# 6-Sensors.net
KiCad netlist of a schematic drawn in Altium Designer
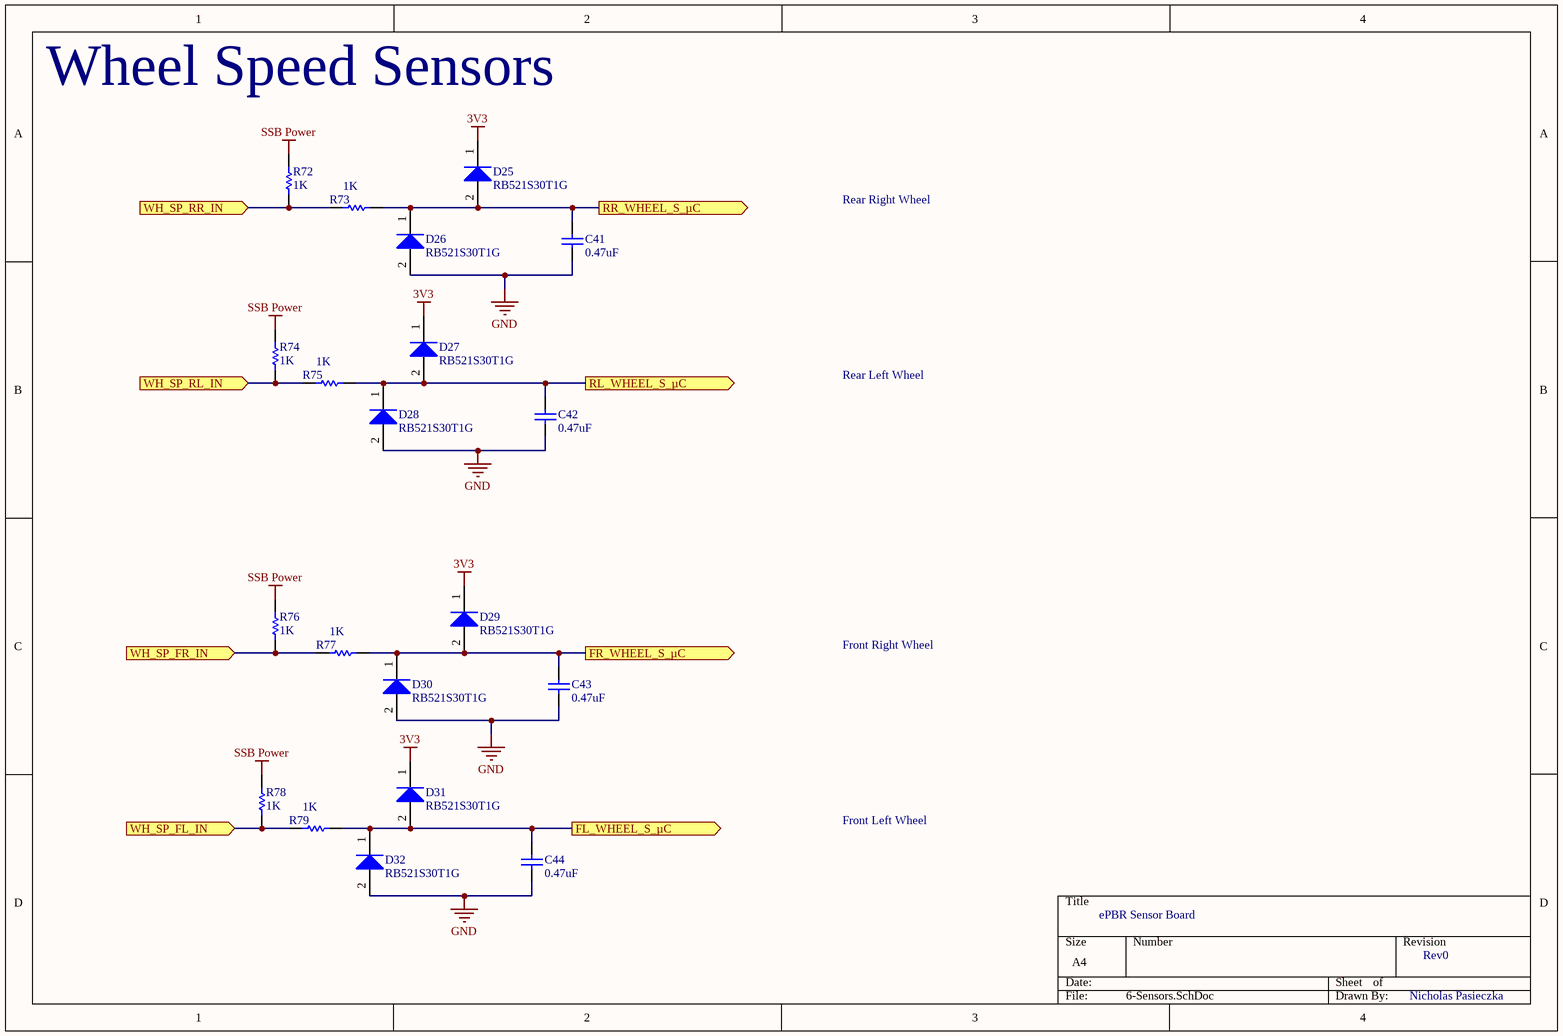
[diagram p0: 6-Sensors.SchDoc]

(export (version "E")
  (design (tool "Eeschema 10.0.6"))
  (components
    (comp (ref "C41")
      (value "0.47uF")
      (footprint "1608[0603]")
      (description "Capacitor")
      (fields (field (name "Comment") "Cap") (field (name "PUBLISHER") "Altium Limited"))
      (libsource (lib "Miscellaneous Devices") (part "Cap"))
    )
    (comp (ref "C42")
      (value "0.47uF")
      (footprint "1608[0603]")
      (description "Capacitor")
      (fields (field (name "Comment") "Cap") (field (name "PUBLISHER") "Altium Limited"))
      (libsource (lib "Miscellaneous Devices") (part "Cap"))
    )
    (comp (ref "C43")
      (value "0.47uF")
      (footprint "1608[0603]")
      (description "Capacitor")
      (fields (field (name "Comment") "Cap") (field (name "PUBLISHER") "Altium Limited"))
      (libsource (lib "Miscellaneous Devices") (part "Cap"))
    )
    (comp (ref "C44")
      (value "0.47uF")
      (footprint "1608[0603]")
      (description "Capacitor")
      (fields (field (name "Comment") "Cap") (field (name "PUBLISHER") "Altium Limited"))
      (libsource (lib "Miscellaneous Devices") (part "Cap"))
    )
    (comp (ref "D25")
      (value "RB521S30T1G")
      (footprint "ONSC-SOD-523-2-502-01_V")
      (description "Schottky Barrier Diode, 2-Pin SOD-523, Pb-Free, Tape and Reel")
      (fields (field (name "MANUFACTURER") "On Semiconductor"))
      (libsource (lib "Altium Content Vault") (part "ONSC-D-K1A2-2"))
    )
    (comp (ref "D26")
      (value "RB521S30T1G")
      (footprint "ONSC-SOD-523-2-502-01_V")
      (description "Schottky Barrier Diode, 2-Pin SOD-523, Pb-Free, Tape and Reel")
      (fields (field (name "MANUFACTURER") "On Semiconductor"))
      (libsource (lib "Altium Content Vault") (part "ONSC-D-K1A2-2"))
    )
    (comp (ref "D27")
      (value "RB521S30T1G")
      (footprint "ONSC-SOD-523-2-502-01_V")
      (description "Schottky Barrier Diode, 2-Pin SOD-523, Pb-Free, Tape and Reel")
      (fields (field (name "MANUFACTURER") "On Semiconductor"))
      (libsource (lib "Altium Content Vault") (part "ONSC-D-K1A2-2"))
    )
    (comp (ref "D28")
      (value "RB521S30T1G")
      (footprint "ONSC-SOD-523-2-502-01_V")
      (description "Schottky Barrier Diode, 2-Pin SOD-523, Pb-Free, Tape and Reel")
      (fields (field (name "MANUFACTURER") "On Semiconductor"))
      (libsource (lib "Altium Content Vault") (part "ONSC-D-K1A2-2"))
    )
    (comp (ref "D29")
      (value "RB521S30T1G")
      (footprint "ONSC-SOD-523-2-502-01_V")
      (description "Schottky Barrier Diode, 2-Pin SOD-523, Pb-Free, Tape and Reel")
      (fields (field (name "MANUFACTURER") "On Semiconductor"))
      (libsource (lib "Altium Content Vault") (part "ONSC-D-K1A2-2"))
    )
    (comp (ref "D30")
      (value "RB521S30T1G")
      (footprint "ONSC-SOD-523-2-502-01_V")
      (description "Schottky Barrier Diode, 2-Pin SOD-523, Pb-Free, Tape and Reel")
      (fields (field (name "MANUFACTURER") "On Semiconductor"))
      (libsource (lib "Altium Content Vault") (part "ONSC-D-K1A2-2"))
    )
    (comp (ref "D31")
      (value "RB521S30T1G")
      (footprint "ONSC-SOD-523-2-502-01_V")
      (description "Schottky Barrier Diode, 2-Pin SOD-523, Pb-Free, Tape and Reel")
      (fields (field (name "MANUFACTURER") "On Semiconductor"))
      (libsource (lib "Altium Content Vault") (part "ONSC-D-K1A2-2"))
    )
    (comp (ref "D32")
      (value "RB521S30T1G")
      (footprint "ONSC-SOD-523-2-502-01_V")
      (description "Schottky Barrier Diode, 2-Pin SOD-523, Pb-Free, Tape and Reel")
      (fields (field (name "MANUFACTURER") "On Semiconductor"))
      (libsource (lib "Altium Content Vault") (part "ONSC-D-K1A2-2"))
    )
    (comp (ref "R72")
      (value "1K")
      (footprint "1608[0603]")
      (description "Resistor")
      (fields (field (name "Comment") "Res1") (field (name "PUBLISHER") "Altium Limited"))
      (libsource (lib "Miscellaneous Devices") (part "Res1"))
    )
    (comp (ref "R73")
      (value "1K")
      (footprint "1608[0603]")
      (description "Resistor")
      (fields (field (name "Comment") "Res1") (field (name "PUBLISHER") "Altium Limited"))
      (libsource (lib "Miscellaneous Devices") (part "Res1"))
    )
    (comp (ref "R74")
      (value "1K")
      (footprint "1608[0603]")
      (description "Resistor")
      (fields (field (name "Comment") "Res1") (field (name "PUBLISHER") "Altium Limited"))
      (libsource (lib "Miscellaneous Devices") (part "Res1"))
    )
    (comp (ref "R75")
      (value "1K")
      (footprint "1608[0603]")
      (description "Resistor")
      (fields (field (name "Comment") "Res1") (field (name "PUBLISHER") "Altium Limited"))
      (libsource (lib "Miscellaneous Devices") (part "Res1"))
    )
    (comp (ref "R76")
      (value "1K")
      (footprint "1608[0603]")
      (description "Resistor")
      (fields (field (name "Comment") "Res1") (field (name "PUBLISHER") "Altium Limited"))
      (libsource (lib "Miscellaneous Devices") (part "Res1"))
    )
    (comp (ref "R77")
      (value "1K")
      (footprint "1608[0603]")
      (description "Resistor")
      (fields (field (name "Comment") "Res1") (field (name "PUBLISHER") "Altium Limited"))
      (libsource (lib "Miscellaneous Devices") (part "Res1"))
    )
    (comp (ref "R78")
      (value "1K")
      (footprint "1608[0603]")
      (description "Resistor")
      (fields (field (name "Comment") "Res1") (field (name "PUBLISHER") "Altium Limited"))
      (libsource (lib "Miscellaneous Devices") (part "Res1"))
    )
    (comp (ref "R79")
      (value "1K")
      (footprint "1608[0603]")
      (description "Resistor")
      (fields (field (name "Comment") "Res1") (field (name "PUBLISHER") "Altium Limited"))
      (libsource (lib "Miscellaneous Devices") (part "Res1"))
    )
  )
  (nets
    (net (code "1") (name "/FL_WHEEL_S_µC") (class "Default")
      (node (ref "C44") (pin "2") (pinfunction "2_2") (pintype "passive"))
      (node (ref "D31") (pin "2") (pinfunction "A_2") (pintype "passive"))
      (node (ref "D32") (pin "1") (pinfunction "K_1") (pintype "passive"))
      (node (ref "R79") (pin "2") (pinfunction "2_2") (pintype "passive"))
    )
    (net (code "2") (name "/FR_WHEEL_S_µC") (class "Default")
      (node (ref "C43") (pin "2") (pinfunction "2_2") (pintype "passive"))
      (node (ref "D29") (pin "2") (pinfunction "A_2") (pintype "passive"))
      (node (ref "D30") (pin "1") (pinfunction "K_1") (pintype "passive"))
      (node (ref "R77") (pin "2") (pinfunction "2_2") (pintype "passive"))
    )
    (net (code "3") (name "/RL_WHEEL_S_µC") (class "Default")
      (node (ref "C42") (pin "2") (pinfunction "2_2") (pintype "passive"))
      (node (ref "D27") (pin "2") (pinfunction "A_2") (pintype "passive"))
      (node (ref "D28") (pin "1") (pinfunction "K_1") (pintype "passive"))
      (node (ref "R75") (pin "2") (pinfunction "2_2") (pintype "passive"))
    )
    (net (code "4") (name "/RR_WHEEL_S_µC") (class "Default")
      (node (ref "C41") (pin "2") (pinfunction "2_2") (pintype "passive"))
      (node (ref "D25") (pin "2") (pinfunction "A_2") (pintype "passive"))
      (node (ref "D26") (pin "1") (pinfunction "K_1") (pintype "passive"))
      (node (ref "R73") (pin "2") (pinfunction "2_2") (pintype "passive"))
    )
    (net (code "5") (name "/WH_SP_FL_IN") (class "Default")
      (node (ref "R78") (pin "1") (pinfunction "1_1") (pintype "passive"))
      (node (ref "R79") (pin "1") (pinfunction "1_1") (pintype "passive"))
    )
    (net (code "6") (name "/WH_SP_FR_IN") (class "Default")
      (node (ref "R76") (pin "1") (pinfunction "1_1") (pintype "passive"))
      (node (ref "R77") (pin "1") (pinfunction "1_1") (pintype "passive"))
    )
    (net (code "7") (name "/WH_SP_RL_IN") (class "Default")
      (node (ref "R74") (pin "1") (pinfunction "1_1") (pintype "passive"))
      (node (ref "R75") (pin "1") (pinfunction "1_1") (pintype "passive"))
    )
    (net (code "8") (name "/WH_SP_RR_IN") (class "Default")
      (node (ref "R72") (pin "1") (pinfunction "1_1") (pintype "passive"))
      (node (ref "R73") (pin "1") (pinfunction "1_1") (pintype "passive"))
    )
    (net (code "9") (name "3V3") (class "Default")
      (node (ref "D25") (pin "1") (pinfunction "K_1") (pintype "passive"))
      (node (ref "D27") (pin "1") (pinfunction "K_1") (pintype "passive"))
      (node (ref "D29") (pin "1") (pinfunction "K_1") (pintype "passive"))
      (node (ref "D31") (pin "1") (pinfunction "K_1") (pintype "passive"))
    )
    (net (code "10") (name "GND") (class "Default")
      (node (ref "C41") (pin "1") (pinfunction "1_1") (pintype "passive"))
      (node (ref "C42") (pin "1") (pinfunction "1_1") (pintype "passive"))
      (node (ref "C43") (pin "1") (pinfunction "1_1") (pintype "passive"))
      (node (ref "C44") (pin "1") (pinfunction "1_1") (pintype "passive"))
      (node (ref "D26") (pin "2") (pinfunction "A_2") (pintype "passive"))
      (node (ref "D28") (pin "2") (pinfunction "A_2") (pintype "passive"))
      (node (ref "D30") (pin "2") (pinfunction "A_2") (pintype "passive"))
      (node (ref "D32") (pin "2") (pinfunction "A_2") (pintype "passive"))
    )
    (net (code "11") (name "SSB Power") (class "Default")
      (node (ref "R72") (pin "2") (pinfunction "2_2") (pintype "passive"))
      (node (ref "R74") (pin "2") (pinfunction "2_2") (pintype "passive"))
      (node (ref "R76") (pin "2") (pinfunction "2_2") (pintype "passive"))
      (node (ref "R78") (pin "2") (pinfunction "2_2") (pintype "passive"))
    )
  )
)
